# motor_driver_1.net
KiCad netlist of a schematic drawn in Altium Designer
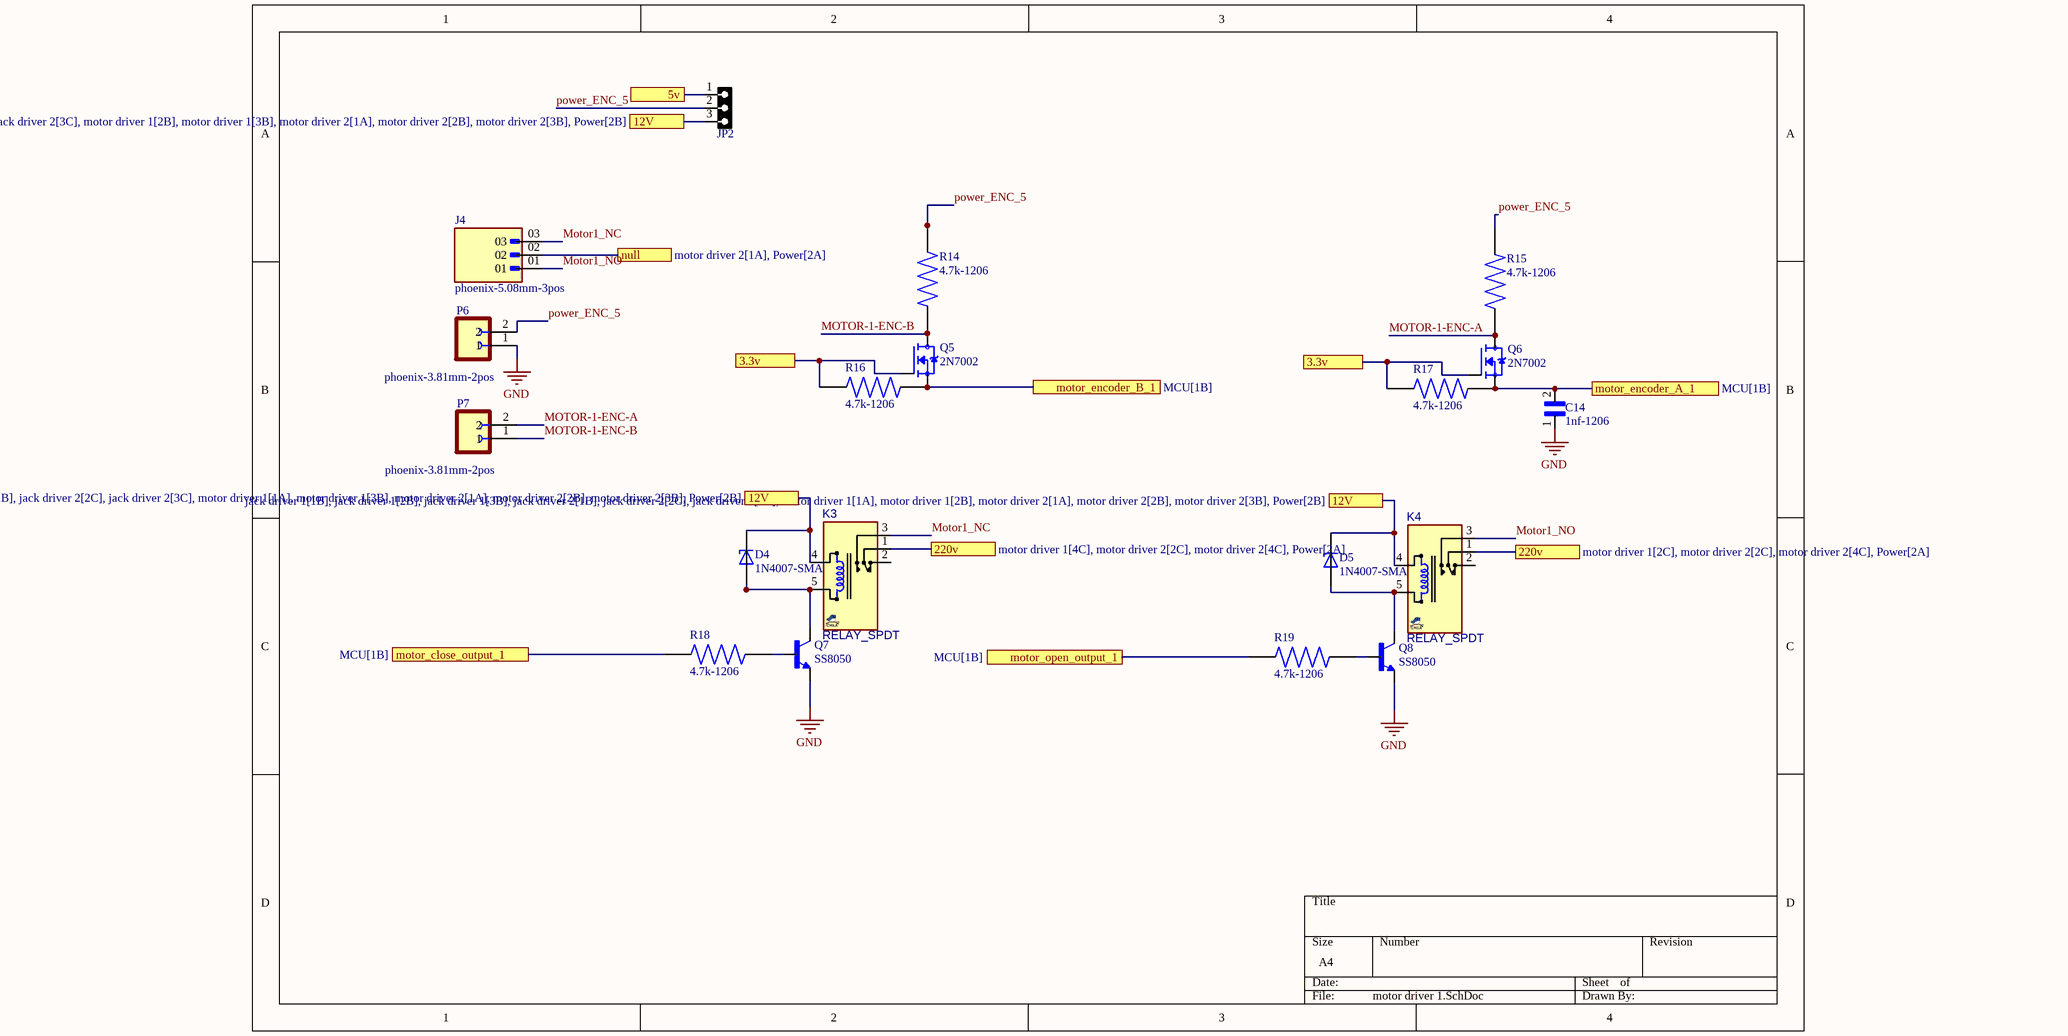
[diagram p0: motor driver 1.SchDoc]

(export (version "E")
  (design (tool "Eeschema 10.0.6"))
  (components
    (comp (ref "C14")
      (value "1nf-1206")
      (footprint "CAPC3216X180N")
      (description "1ÂµF Â±20% 50V Ceramic Capacitor X8R 1206 (3216 Metric)")
      (fields (field (name "MF") "TDK") (field (name "MP") "CGA5L3X8R1H105M160AB"))
      (libsource (lib "cap-1206") (part "CGA5L3X8R1H105M160AB"))
    )
    (comp (ref "D4")
      (value "1N4007-SMA")
      (footprint "DIOM4325X250N")
      (description "400W, 30.4V, 5%, Unidirectional, TVS")
      (fields (field (name "MF") "Taiwan Semiconductor") (field (name "MP") "SMAJ26A"))
      (libsource (lib "diode-sma") (part "SMAJ26A"))
    )
    (comp (ref "D5")
      (value "1N4007-SMA")
      (footprint "DIOM4325X250N")
      (description "400W, 30.4V, 5%, Unidirectional, TVS")
      (fields (field (name "MF") "Taiwan Semiconductor") (field (name "MP") "SMAJ26A"))
      (libsource (lib "diode-sma") (part "SMAJ26A"))
    )
    (comp (ref "J4")
      (value "phoenix-5.08mm-3pos")
      (footprint "PHOENIX_1759020")
      (description "Pluggable Header 5.08mm 12AWG 320V 12A 3 Position COMBICON MSTB Series ¦ Phoenix Contact 1759020")
      (fields (field (name "MF") "Phoenix Contact") (field (name "MP") "1759020"))
      (libsource (lib "phoenix-3pos") (part "1759020"))
    )
    (comp (ref "JP2")
      (value "HDRF3")
      (footprint "HDRLP_F_1X3")
      (description "CONN, HEADER, Male, pitch: 2.54mm, 3POS")
      (libsource (lib "conn_2.54mm_lp") (part "HDRLP_F_1X3"))
    )
    (comp (ref "K3")
      (value "RELAY_SPDT")
      (footprint "REL_SPDT_5_1512")
      (description "Relay, SPDT, 5P, 15.4X12.1mm, 16V/30A")
      (fields (field (name "MANF") "OMRON") (field (name "MANF_P#") "G8QN-1C4 DC12"))
      (libsource (lib "relay") (part "RELAY_SPDT_5_1512_G8QN"))
    )
    (comp (ref "K4")
      (value "RELAY_SPDT")
      (footprint "REL_SPDT_5_1512")
      (description "Relay, SPDT, 5P, 15.4X12.1mm, 16V/30A")
      (fields (field (name "MANF") "OMRON") (field (name "MANF_P#") "G8QN-1C4 DC12"))
      (libsource (lib "relay") (part "RELAY_SPDT_5_1512_G8QN"))
    )
    (comp (ref "P6")
      (value "phoenix-3.81mm-2pos")
      (footprint "PHOENIX_1803578")
      (description "2 Position Terminal Block Plug, Female Sockets 0.150 (3.81mm) 180Â° Free Hanging (In-Line)")
      (fields (field (name "MF") "Phoenix Contact") (field (name "MP") "1803578"))
      (libsource (lib "terminal-phoenix-3.81mm-2pos") (part "1803578"))
    )
    (comp (ref "P7")
      (value "phoenix-3.81mm-2pos")
      (footprint "PHOENIX_1803578")
      (description "2 Position Terminal Block Plug, Female Sockets 0.150 (3.81mm) 180Â° Free Hanging (In-Line)")
      (fields (field (name "MF") "Phoenix Contact") (field (name "MP") "1803578"))
      (libsource (lib "terminal-phoenix-3.81mm-2pos") (part "1803578"))
    )
    (comp (ref "Q5")
      (value "2N7002")
      (footprint "SOT95P240X111-3N")
      (description "N-Channel 60V 280mA (Ta) 350mW (Ta) Surface Mount SOT-23-3 (TO-236)")
      (fields (field (name "MF") "{'manufacturer': u'onsemi'}"))
      (libsource (lib "2N7002-SOT23") (part "2N7002"))
    )
    (comp (ref "Q6")
      (value "2N7002")
      (footprint "SOT95P240X111-3N")
      (description "N-Channel 60V 280mA (Ta) 350mW (Ta) Surface Mount SOT-23-3 (TO-236)")
      (fields (field (name "MF") "{'manufacturer': u'onsemi'}"))
      (libsource (lib "2N7002-SOT23") (part "2N7002"))
    )
    (comp (ref "Q7")
      (value "SS8050")
      (footprint "TRANS_SS8050-G")
      (description "Bipolar (BJT) Transistor NPN 25 V 1.5 A 100MHz 300 mW Surface Mount SOT-23-3")
      (fields (field (name "DIGI-KEY_PART_NUMBER") "641-1790-2-ND") (field (name "MP") "SS8050G"))
      (libsource (lib "SS8050-G") (part "SS8050-G"))
    )
    (comp (ref "Q8")
      (value "SS8050")
      (footprint "TRANS_SS8050-G")
      (description "Bipolar (BJT) Transistor NPN 25 V 1.5 A 100MHz 300 mW Surface Mount SOT-23-3")
      (fields (field (name "DIGI-KEY_PART_NUMBER") "641-1790-2-ND") (field (name "MP") "SS8050G"))
      (libsource (lib "SS8050-G") (part "SS8050-G"))
    )
    (comp (ref "R14")
      (value "4.7k-1206")
      (footprint "RESC3015X65N")
      (description "Res Thin Film 1206 10K Ohm 0.1% 1/8W Â±25ppm/Â°C Molded SMD SMD Paper T/R")
      (fields (field (name "MF") "TE Connectivity") (field (name "MP") "CPF1206B10KE1"))
      (libsource (lib "resistor-1206") (part "CPF1206B10KE1"))
    )
    (comp (ref "R15")
      (value "4.7k-1206")
      (footprint "RESC3015X65N")
      (description "Res Thin Film 1206 10K Ohm 0.1% 1/8W Â±25ppm/Â°C Molded SMD SMD Paper T/R")
      (fields (field (name "MF") "TE Connectivity") (field (name "MP") "CPF1206B10KE1"))
      (libsource (lib "resistor-1206") (part "CPF1206B10KE1"))
    )
    (comp (ref "R16")
      (value "4.7k-1206")
      (footprint "RESC3015X65N")
      (description "Res Thin Film 1206 10K Ohm 0.1% 1/8W Â±25ppm/Â°C Molded SMD SMD Paper T/R")
      (fields (field (name "MF") "TE Connectivity") (field (name "MP") "CPF1206B10KE1"))
      (libsource (lib "resistor-1206") (part "CPF1206B10KE1"))
    )
    (comp (ref "R17")
      (value "4.7k-1206")
      (footprint "RESC3015X65N")
      (description "Res Thin Film 1206 10K Ohm 0.1% 1/8W Â±25ppm/Â°C Molded SMD SMD Paper T/R")
      (fields (field (name "MF") "TE Connectivity") (field (name "MP") "CPF1206B10KE1"))
      (libsource (lib "resistor-1206") (part "CPF1206B10KE1"))
    )
    (comp (ref "R18")
      (value "4.7k-1206")
      (footprint "RESC3015X65N")
      (description "Res Thin Film 1206 10K Ohm 0.1% 1/8W Â±25ppm/Â°C Molded SMD SMD Paper T/R")
      (fields (field (name "MF") "TE Connectivity") (field (name "MP") "CPF1206B10KE1"))
      (libsource (lib "resistor-1206") (part "CPF1206B10KE1"))
    )
    (comp (ref "R19")
      (value "4.7k-1206")
      (footprint "RESC3015X65N")
      (description "Res Thin Film 1206 10K Ohm 0.1% 1/8W Â±25ppm/Â°C Molded SMD SMD Paper T/R")
      (fields (field (name "MF") "TE Connectivity") (field (name "MP") "CPF1206B10KE1"))
      (libsource (lib "resistor-1206") (part "CPF1206B10KE1"))
    )
  )
  (nets
    (net (code "1") (name "/3.3v") (class "Default")
      (node (ref "Q5") (pin "1") (pinfunction "G_1") (pintype "passive"))
      (node (ref "Q6") (pin "1") (pinfunction "G_1") (pintype "passive"))
      (node (ref "R16") (pin "2") (pinfunction "2_2") (pintype "passive"))
      (node (ref "R17") (pin "2") (pinfunction "2_2") (pintype "passive"))
    )
    (net (code "2") (name "/5v") (class "Default")
      (node (ref "JP2") (pin "1") (pinfunction "1_1") (pintype "passive"))
    )
    (net (code "3") (name "/12V") (class "Default")
      (node (ref "D4") (pin "C") (pinfunction "C_C") (pintype "passive"))
      (node (ref "D5") (pin "C") (pinfunction "C_C") (pintype "passive"))
      (node (ref "JP2") (pin "3") (pinfunction "3_3") (pintype "passive"))
      (node (ref "K3") (pin "4") (pinfunction "T1_4") (pintype "passive"))
      (node (ref "K4") (pin "4") (pinfunction "T1_4") (pintype "passive"))
    )
    (net (code "4") (name "/220v") (class "Default")
      (node (ref "K3") (pin "1") (pinfunction "COM_1") (pintype "passive"))
      (node (ref "K4") (pin "1") (pinfunction "COM_1") (pintype "passive"))
    )
    (net (code "5") (name "/MOTOR-1-ENC-A") (class "Default")
      (node (ref "P7") (pin "2") (pinfunction "2_2") (pintype "passive"))
      (node (ref "Q6") (pin "3") (pinfunction "D_3") (pintype "passive"))
      (node (ref "R15") (pin "1") (pinfunction "1_1") (pintype "passive"))
    )
    (net (code "6") (name "/MOTOR-1-ENC-B") (class "Default")
      (node (ref "P7") (pin "1") (pinfunction "1_1") (pintype "passive"))
      (node (ref "Q5") (pin "3") (pinfunction "D_3") (pintype "passive"))
      (node (ref "R14") (pin "1") (pinfunction "1_1") (pintype "passive"))
    )
    (net (code "7") (name "/Motor1_NC") (class "Default")
      (node (ref "J4") (pin "03") (pinfunction "03_03") (pintype "passive"))
      (node (ref "K3") (pin "3") (pinfunction "NO_3") (pintype "passive"))
    )
    (net (code "8") (name "/Motor1_NO") (class "Default")
      (node (ref "J4") (pin "01") (pinfunction "01_01") (pintype "passive"))
      (node (ref "K4") (pin "3") (pinfunction "NO_3") (pintype "passive"))
    )
    (net (code "9") (name "/motor_close_output_1") (class "Default")
      (node (ref "R18") (pin "2") (pinfunction "2_2") (pintype "passive"))
    )
    (net (code "10") (name "/motor_encoder_A_1") (class "Default")
      (node (ref "C14") (pin "2") (pinfunction "2_2") (pintype "passive"))
      (node (ref "Q6") (pin "2") (pinfunction "S_2") (pintype "passive"))
      (node (ref "R17") (pin "1") (pinfunction "1_1") (pintype "passive"))
    )
    (net (code "11") (name "/motor_encoder_B_1") (class "Default")
      (node (ref "Q5") (pin "2") (pinfunction "S_2") (pintype "passive"))
      (node (ref "R16") (pin "1") (pinfunction "1_1") (pintype "passive"))
    )
    (net (code "12") (name "/motor_open_output_1") (class "Default")
      (node (ref "R19") (pin "2") (pinfunction "2_2") (pintype "passive"))
    )
    (net (code "13") (name "/null") (class "Default")
      (node (ref "J4") (pin "02") (pinfunction "02_02") (pintype "passive"))
    )
    (net (code "14") (name "/power_ENC_5") (class "Default")
      (node (ref "JP2") (pin "2") (pinfunction "2_2") (pintype "passive"))
      (node (ref "P6") (pin "2") (pinfunction "2_2") (pintype "passive"))
      (node (ref "R14") (pin "2") (pinfunction "2_2") (pintype "passive"))
      (node (ref "R15") (pin "2") (pinfunction "2_2") (pintype "passive"))
    )
    (net (code "15") (name "GND") (class "Default")
      (node (ref "C14") (pin "1") (pinfunction "1_1") (pintype "passive"))
      (node (ref "P6") (pin "1") (pinfunction "1_1") (pintype "passive"))
      (node (ref "Q7") (pin "2") (pinfunction "E_2") (pintype "passive"))
      (node (ref "Q8") (pin "2") (pinfunction "E_2") (pintype "passive"))
    )
    (net (code "16") (name "Net-(K3-T2)") (class "Default")
      (node (ref "D4") (pin "A") (pinfunction "A_A") (pintype "passive"))
      (node (ref "K3") (pin "5") (pinfunction "T2_5") (pintype "passive"))
      (node (ref "Q7") (pin "3") (pinfunction "C_3") (pintype "passive"))
    )
    (net (code "17") (name "Net-(K4-T2)") (class "Default")
      (node (ref "D5") (pin "A") (pinfunction "A_A") (pintype "passive"))
      (node (ref "K4") (pin "5") (pinfunction "T2_5") (pintype "passive"))
      (node (ref "Q8") (pin "3") (pinfunction "C_3") (pintype "passive"))
    )
    (net (code "18") (name "Net-(Q7-B)") (class "Default")
      (node (ref "Q7") (pin "1") (pinfunction "B_1") (pintype "passive"))
      (node (ref "R18") (pin "1") (pinfunction "1_1") (pintype "passive"))
    )
    (net (code "19") (name "Net-(Q8-B)") (class "Default")
      (node (ref "Q8") (pin "1") (pinfunction "B_1") (pintype "passive"))
      (node (ref "R19") (pin "1") (pinfunction "1_1") (pintype "passive"))
    )
    (net (code "20") (name "unconnected-(K3-NC-Pad2)") (class "Default")
      (node (ref "K3") (pin "2") (pinfunction "NC_2") (pintype "passive"))
    )
    (net (code "21") (name "unconnected-(K4-NC-Pad2)") (class "Default")
      (node (ref "K4") (pin "2") (pinfunction "NC_2") (pintype "passive"))
    )
  )
)
